# IO_Expansioin.net
KiCad netlist of a schematic drawn in Altium Designer
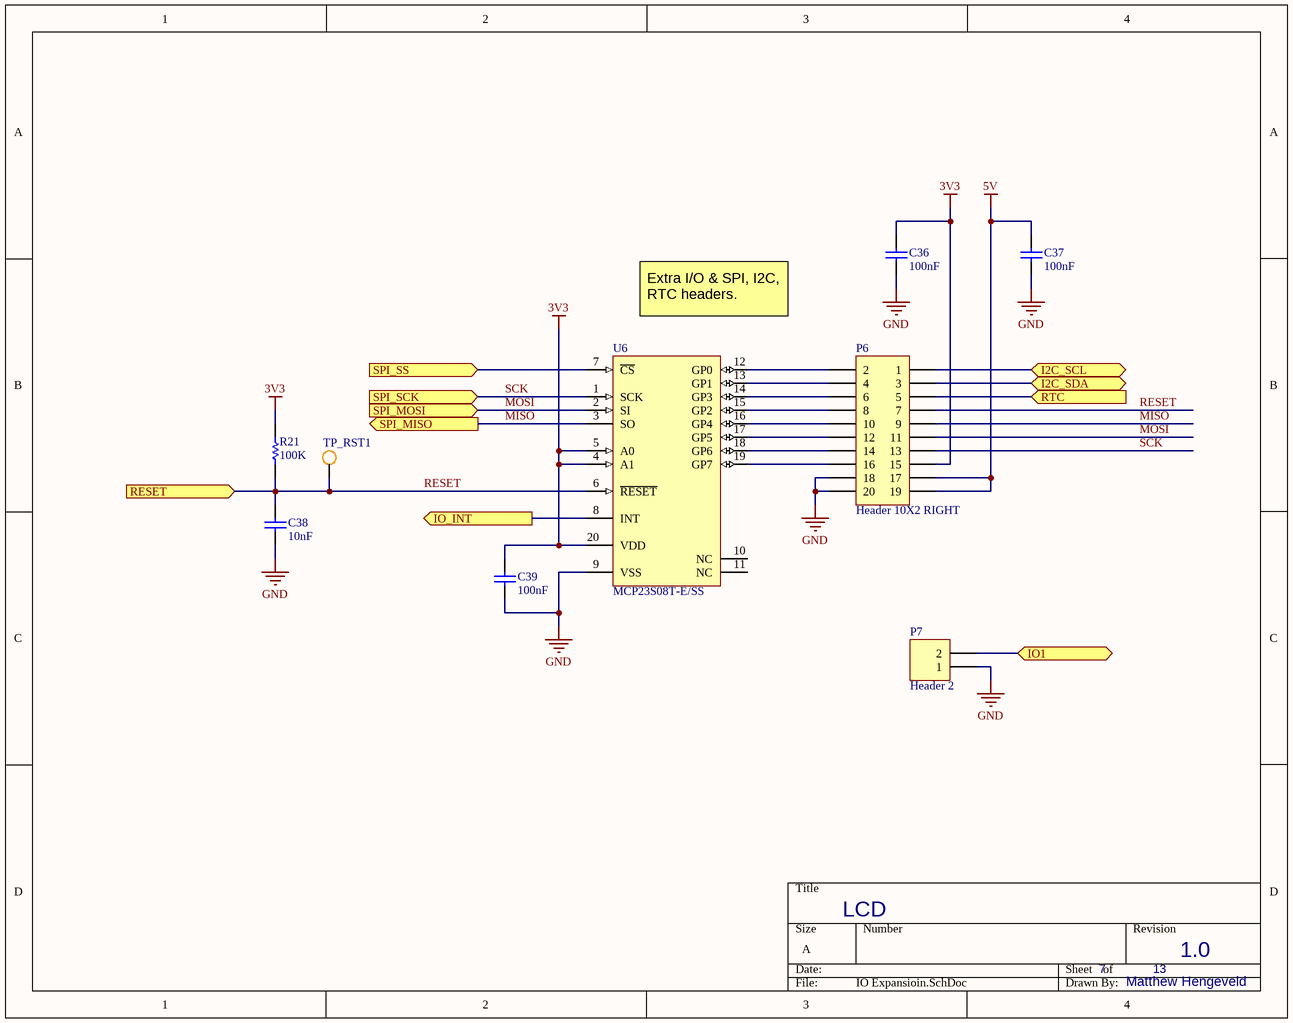
[diagram p0: IO Expansioin.SchDoc]

(export (version "E")
  (design (tool "Eeschema 10.0.6"))
  (components
    (comp (ref "C36")
      (value "100nF")
      (footprint "CAPC1608X92X38LL15T08")
      (fields (field (name "PART NUMBER") "VJ0603Y104KNXAO") (field (name "MANUFACTURER") "Vitramon"))
      (libsource (lib "Altium Content Vault") (part "CAP"))
    )
    (comp (ref "C37")
      (value "100nF")
      (footprint "CAPC1608X92X38LL15T08")
      (fields (field (name "PART NUMBER") "VJ0603Y104KNXAO") (field (name "MANUFACTURER") "Vitramon"))
      (libsource (lib "Altium Content Vault") (part "CAP"))
    )
    (comp (ref "C38")
      (value "10nF")
      (footprint "CAPC1608X92X38LL15T08")
      (fields (field (name "PART NUMBER") "VJ0603Y104KNXAO") (field (name "MANUFACTURER") "Vitramon"))
      (libsource (lib "Altium Content Vault") (part "CAP"))
    )
    (comp (ref "C39")
      (value "100nF")
      (footprint "CAPC1608X92X38LL15T08")
      (fields (field (name "PART NUMBER") "VJ0603Y104KNXAO") (field (name "MANUFACTURER") "Vitramon"))
      (libsource (lib "Altium Content Vault") (part "CAP"))
    )
    (comp (ref "P6")
      (value "Header 10X2 RIGHT")
      (footprint "HDR2X10 RIGHT")
      (description "Header, 10-Pin, Dual row, Right Angle")
      (fields (field (name "PUBLISHER") "Altium Limited"))
      (libsource (lib "Hengeveld") (part "Header 10X2 RIGHT"))
    )
    (comp (ref "P7")
      (value "Header 2")
      (footprint "HDR1X2")
      (description "Header, 2-Pin")
      (fields (field (name "PUBLISHER") "Altium Limited"))
      (libsource (lib "Hengeveld") (part "Header 2"))
    )
    (comp (ref "R21")
      (value "100K")
      (footprint "RESC1608X55X30LL15T15")
      (fields (field (name "MANUFACTURER") "Panasonic") (field (name "PART NUMBER") "ERJ-3GEYJ103V"))
      (libsource (lib "Altium Content Vault") (part "RES"))
    )
    (comp (ref "TP_RST1")
      (value "Test point")
      (footprint "SMD Test Hook")
      (libsource (lib "Hengeveld") (part "Test Point"))
    )
    (comp (ref "U6")
      (value "MCP23S08T-E/SS")
      (footprint "SSOP-20")
      (description "8-Bit I/O Expander with Serial Interface, 20-Pin SSOP, Extended Temperature, Tape and Reel")
      (libsource (lib "Hengeveld") (part "CMP-0186-00165-3"))
    )
  )
  (nets
    (net (code "1") (name "/I2C_SCL") (class "Default")
      (node (ref "P6") (pin "1") (pinfunction "1_1") (pintype "passive"))
    )
    (net (code "2") (name "/I2C_SDA") (class "Default")
      (node (ref "P6") (pin "3") (pinfunction "3_3") (pintype "passive"))
    )
    (net (code "3") (name "/IO1") (class "Default")
      (node (ref "P7") (pin "2") (pinfunction "2_2") (pintype "passive"))
    )
    (net (code "4") (name "/IO_INT") (class "Default")
      (node (ref "U6") (pin "8") (pinfunction "INT_8") (pintype "open_collector"))
    )
    (net (code "5") (name "/MISO") (class "Default")
      (node (ref "P6") (pin "9") (pinfunction "9_9") (pintype "passive"))
      (node (ref "U6") (pin "3") (pinfunction "SO_3") (pintype "tri_state"))
    )
    (net (code "6") (name "/MOSI") (class "Default")
      (node (ref "P6") (pin "11") (pinfunction "11_11") (pintype "passive"))
      (node (ref "U6") (pin "2") (pinfunction "SI_2") (pintype "input"))
    )
    (net (code "7") (name "/RESET") (class "Default")
      (node (ref "C38") (pin "2") (pinfunction "2_2") (pintype "passive"))
      (node (ref "P6") (pin "7") (pinfunction "7_7") (pintype "passive"))
      (node (ref "R21") (pin "2") (pinfunction "2_2") (pintype "passive"))
      (node (ref "TP_RST1") (pin "1") (pinfunction "point_1") (pintype "passive"))
      (node (ref "U6") (pin "6") (pinfunction "~{RESET}_6") (pintype "input"))
    )
    (net (code "8") (name "/RTC") (class "Default")
      (node (ref "P6") (pin "5") (pinfunction "5_5") (pintype "passive"))
    )
    (net (code "9") (name "/SCK") (class "Default")
      (node (ref "P6") (pin "13") (pinfunction "13_13") (pintype "passive"))
      (node (ref "U6") (pin "1") (pinfunction "SCK_1") (pintype "input"))
    )
    (net (code "10") (name "/SPI_SS") (class "Default")
      (node (ref "U6") (pin "7") (pinfunction "~{CS}_7") (pintype "input"))
    )
    (net (code "11") (name "3V3") (class "Default")
      (node (ref "C36") (pin "2") (pinfunction "2_2") (pintype "passive"))
      (node (ref "C39") (pin "2") (pinfunction "2_2") (pintype "passive"))
      (node (ref "P6") (pin "15") (pinfunction "15_15") (pintype "passive"))
      (node (ref "R21") (pin "1") (pinfunction "1_1") (pintype "passive"))
      (node (ref "U6") (pin "20") (pinfunction "VDD_20") (pintype "power_in"))
      (node (ref "U6") (pin "4") (pinfunction "A1_4") (pintype "input"))
      (node (ref "U6") (pin "5") (pinfunction "A0_5") (pintype "input"))
    )
    (net (code "12") (name "5V") (class "Default")
      (node (ref "C37") (pin "2") (pinfunction "2_2") (pintype "passive"))
      (node (ref "P6") (pin "17") (pinfunction "17_17") (pintype "passive"))
      (node (ref "P6") (pin "19") (pinfunction "19_19") (pintype "passive"))
    )
    (net (code "13") (name "GND") (class "Default")
      (node (ref "C36") (pin "1") (pinfunction "1_1") (pintype "passive"))
      (node (ref "C37") (pin "1") (pinfunction "1_1") (pintype "passive"))
      (node (ref "C38") (pin "1") (pinfunction "1_1") (pintype "passive"))
      (node (ref "C39") (pin "1") (pinfunction "1_1") (pintype "passive"))
      (node (ref "P6") (pin "18") (pinfunction "18_18") (pintype "passive"))
      (node (ref "P6") (pin "20") (pinfunction "20_20") (pintype "passive"))
      (node (ref "P7") (pin "1") (pinfunction "1_1") (pintype "passive"))
      (node (ref "U6") (pin "9") (pinfunction "VSS_9") (pintype "power_in"))
    )
    (net (code "14") (name "Net-(U6-GP0)") (class "Default")
      (node (ref "P6") (pin "2") (pinfunction "2_2") (pintype "passive"))
      (node (ref "U6") (pin "12") (pinfunction "GP0_12") (pintype "bidirectional"))
    )
    (net (code "15") (name "Net-(U6-GP1)") (class "Default")
      (node (ref "P6") (pin "4") (pinfunction "4_4") (pintype "passive"))
      (node (ref "U6") (pin "13") (pinfunction "GP1_13") (pintype "bidirectional"))
    )
    (net (code "16") (name "Net-(U6-GP2)") (class "Default")
      (node (ref "P6") (pin "8") (pinfunction "8_8") (pintype "passive"))
      (node (ref "U6") (pin "15") (pinfunction "GP2_15") (pintype "bidirectional"))
    )
    (net (code "17") (name "Net-(U6-GP3)") (class "Default")
      (node (ref "P6") (pin "6") (pinfunction "6_6") (pintype "passive"))
      (node (ref "U6") (pin "14") (pinfunction "GP3_14") (pintype "bidirectional"))
    )
    (net (code "18") (name "Net-(U6-GP4)") (class "Default")
      (node (ref "P6") (pin "10") (pinfunction "10_10") (pintype "passive"))
      (node (ref "U6") (pin "16") (pinfunction "GP4_16") (pintype "bidirectional"))
    )
    (net (code "19") (name "Net-(U6-GP5)") (class "Default")
      (node (ref "P6") (pin "12") (pinfunction "12_12") (pintype "passive"))
      (node (ref "U6") (pin "17") (pinfunction "GP5_17") (pintype "bidirectional"))
    )
    (net (code "20") (name "Net-(U6-GP6)") (class "Default")
      (node (ref "P6") (pin "14") (pinfunction "14_14") (pintype "passive"))
      (node (ref "U6") (pin "18") (pinfunction "GP6_18") (pintype "bidirectional"))
    )
    (net (code "21") (name "Net-(U6-GP7)") (class "Default")
      (node (ref "P6") (pin "16") (pinfunction "16_16") (pintype "passive"))
      (node (ref "U6") (pin "19") (pinfunction "GP7_19") (pintype "bidirectional"))
    )
    (net (code "22") (name "unconnected-(U6-NC-Pad10)") (class "Default")
      (node (ref "U6") (pin "10") (pinfunction "NC_10") (pintype "passive"))
    )
    (net (code "23") (name "unconnected-(U6-NC-Pad11)") (class "Default")
      (node (ref "U6") (pin "11") (pinfunction "NC_11") (pintype "passive"))
    )
  )
)
